# boost_regulator.net
KiCad netlist of a schematic drawn in EAGLE
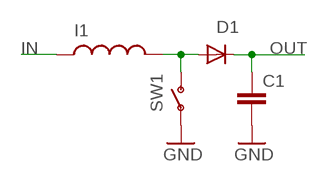
[diagram p0: schematic, sheet 1]

(export (version "E")
  (design (tool "Eeschema 10.0.6"))
  (components
    (comp (ref "C1")
      (value "CAP0402-CAP")
      (footprint "eagle-import:0402-CAP")
      (libsource (lib "eagle-import") (part "CAP0402-CAP"))
    )
    (comp (ref "D1")
      (value "DIODE1N4148")
      (footprint "eagle-import:DIODE-1N4148")
      (libsource (lib "eagle-import") (part "DIODE1N4148"))
    )
    (comp (ref "I1")
      (value "INDUCTOR")
      (footprint "eagle-import:BOURNES_E12")
      (libsource (lib "eagle-import") (part "INDUCTOR"))
    )
    (comp (ref "SW1")
      (value "SWITCH_SPST")
      (footprint "eagle-import:SPST_SMT_19192")
      (libsource (lib "eagle-import") (part "SWITCH_SPST"))
    )
  )
  (nets
    (net (code "1") (name "/IN") (class "Default")
      (node (ref "I1") (pin "P$1") (pinfunction "1_P$1") (pintype "passive"))
    )
    (net (code "2") (name "/OUT") (class "Default")
      (node (ref "C1") (pin "1") (pinfunction "1_1") (pintype "passive"))
      (node (ref "D1") (pin "C") (pinfunction "C_C") (pintype "passive"))
    )
    (net (code "3") (name "GND") (class "Default")
      (node (ref "C1") (pin "2") (pinfunction "2_2") (pintype "passive"))
      (node (ref "SW1") (pin "B") (pinfunction "P_B") (pintype "passive"))
    )
    (net (code "4") (name "Net-(I1-2)") (class "Default")
      (node (ref "D1") (pin "A") (pinfunction "A_A") (pintype "passive"))
      (node (ref "I1") (pin "P$2") (pinfunction "2_P$2") (pintype "passive"))
      (node (ref "SW1") (pin "C") (pinfunction "S_C") (pintype "passive"))
    )
  )
)
